# Grove_-_GSR_v1_0.net
KiCad netlist of a schematic drawn in EAGLE
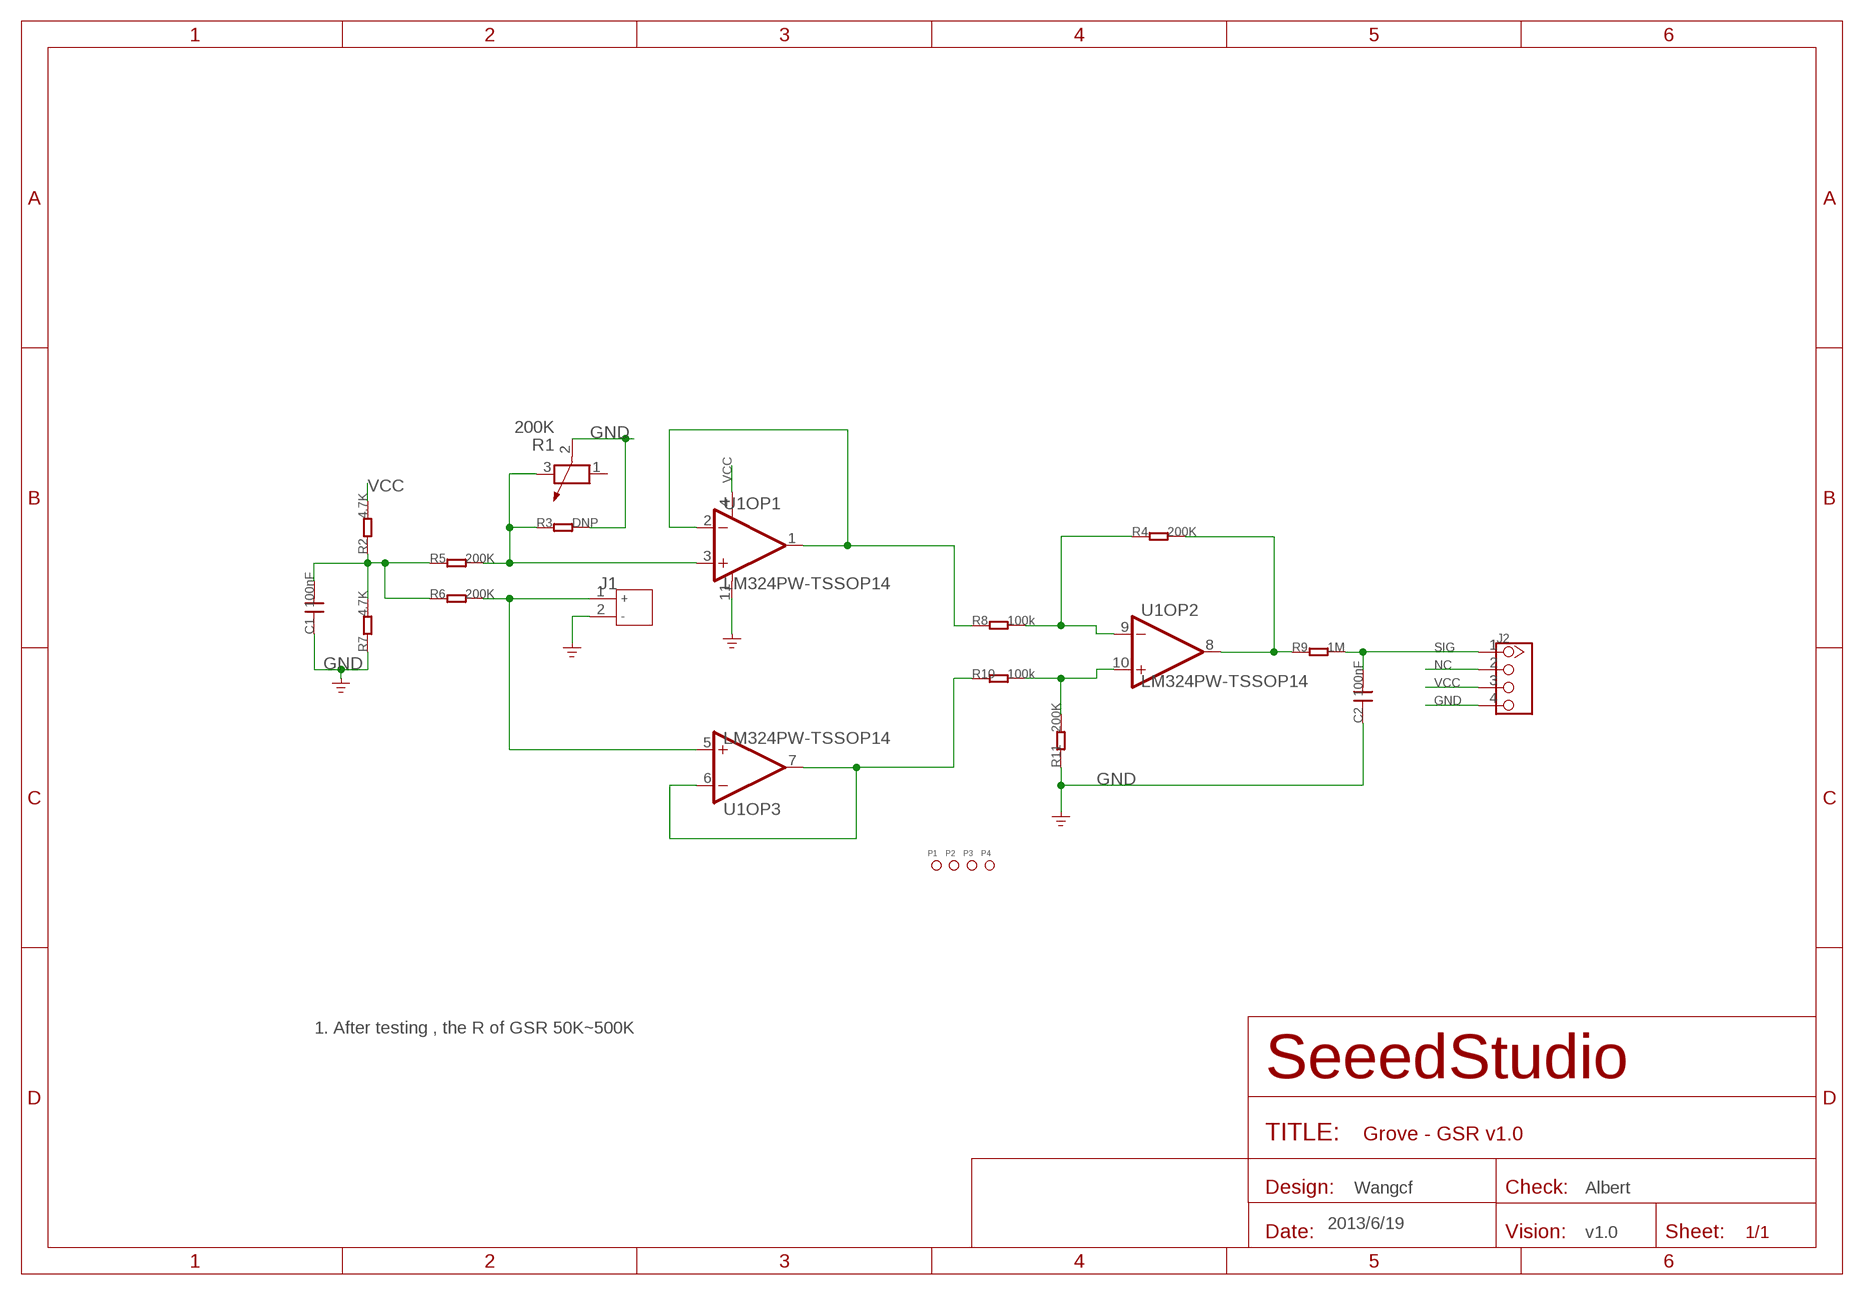
[diagram p0: schematic, sheet 1]

(export (version "E")
  (design (tool "Eeschema 10.0.6"))
  (components
    (comp (ref "C1")
      (value "100nF")
      (footprint "eagle-import:0603")
      (libsource (lib "eagle-import") (part "C-0603"))
    )
    (comp (ref "C2")
      (value "100nF")
      (footprint "eagle-import:0603")
      (libsource (lib "eagle-import") (part "C-0603"))
    )
    (comp (ref "J1")
      (value "JACK-JST-2P-PW'2.0'")
      (footprint "eagle-import:JST-2.0")
      (libsource (lib "eagle-import") (part "JACK-JST-2P-PW'2.0'"))
    )
    (comp (ref "J2")
      (value "TWIG-4P-2.0-2.0")
      (footprint "eagle-import:4P-2.0")
      (libsource (lib "eagle-import") (part "TWIG-4P-2.0-2.0"))
    )
    (comp (ref "P1")
      (value "PAD-MARK")
      (footprint "eagle-import:ROUND-MARK-1.0")
      (fields (field (name "PARTNO") "DNP"))
      (libsource (lib "eagle-import") (part "PAD-MARK"))
    )
    (comp (ref "P2")
      (value "PAD-MARK")
      (footprint "eagle-import:ROUND-MARK-1.0")
      (fields (field (name "PARTNO") "DNP"))
      (libsource (lib "eagle-import") (part "PAD-MARK"))
    )
    (comp (ref "P3")
      (value "PAD-MARK")
      (footprint "eagle-import:ROUND-MARK-1.0")
      (fields (field (name "PARTNO") "DNP"))
      (libsource (lib "eagle-import") (part "PAD-MARK"))
    )
    (comp (ref "P4")
      (value "PAD-MARK")
      (footprint "eagle-import:ROUND-MARK-1.0")
      (fields (field (name "PARTNO") "DNP"))
      (libsource (lib "eagle-import") (part "PAD-MARK"))
    )
    (comp (ref "R1")
      (value "200K")
      (footprint "eagle-import:3P-SMD-RECT-3.3X3.6")
      (libsource (lib "eagle-import") (part "R-POTENTIOMETER-SMD"))
    )
    (comp (ref "R2")
      (value "4.7K")
      (footprint "eagle-import:0603")
      (libsource (lib "eagle-import") (part "R-0603"))
    )
    (comp (ref "R3")
      (value "DNP")
      (footprint "eagle-import:0603")
      (libsource (lib "eagle-import") (part "R-0603"))
    )
    (comp (ref "R4")
      (value "200K")
      (footprint "eagle-import:0603")
      (libsource (lib "eagle-import") (part "R-0603"))
    )
    (comp (ref "R5")
      (value "200K")
      (footprint "eagle-import:0603")
      (libsource (lib "eagle-import") (part "R-0603"))
    )
    (comp (ref "R6")
      (value "200K")
      (footprint "eagle-import:0603")
      (libsource (lib "eagle-import") (part "R-0603"))
    )
    (comp (ref "R7")
      (value "4.7K")
      (footprint "eagle-import:0603")
      (libsource (lib "eagle-import") (part "R-0603"))
    )
    (comp (ref "R8")
      (value "100k")
      (footprint "eagle-import:0603")
      (libsource (lib "eagle-import") (part "R-0603"))
    )
    (comp (ref "R9")
      (value "1M")
      (footprint "eagle-import:0603")
      (libsource (lib "eagle-import") (part "R-0603"))
    )
    (comp (ref "R10")
      (value "100k")
      (footprint "eagle-import:0603")
      (libsource (lib "eagle-import") (part "R-0603"))
    )
    (comp (ref "R11")
      (value "200K")
      (footprint "eagle-import:0603")
      (libsource (lib "eagle-import") (part "R-0603"))
    )
    (comp (ref "U1")
      (value "LM324PW-TSSOP14")
      (footprint "eagle-import:TSSOP14")
      (libsource (lib "eagle-import") (part "LMV324-TSSOP14"))
    )
  )
  (nets
    (net (code "1") (name "/NC") (class "Default")
      (node (ref "J2") (pin "2") (pinfunction "2_2") (pintype "bidirectional"))
    )
    (net (code "2") (name "/SIG") (class "Default")
      (node (ref "C2") (pin "2") (pinfunction "2_2") (pintype "passive"))
      (node (ref "J2") (pin "1") (pinfunction "1_1") (pintype "bidirectional"))
      (node (ref "R9") (pin "2") (pinfunction "2_2") (pintype "passive"))
    )
    (net (code "3") (name "/VCC") (class "Default")
      (node (ref "J2") (pin "3") (pinfunction "3_3") (pintype "bidirectional"))
      (node (ref "R2") (pin "2") (pinfunction "2_2") (pintype "passive"))
      (node (ref "U1") (pin "4") (pinfunction "V+_4") (pintype "power_in"))
    )
    (net (code "4") (name "GND_POWER") (class "Default")
      (node (ref "C1") (pin "1") (pinfunction "1_1") (pintype "passive"))
      (node (ref "C2") (pin "1") (pinfunction "1_1") (pintype "passive"))
      (node (ref "J1") (pin "2") (pinfunction "P$2_2") (pintype "bidirectional"))
      (node (ref "J2") (pin "4") (pinfunction "4_4") (pintype "bidirectional"))
      (node (ref "R1") (pin "2") (pinfunction "3_2") (pintype "passive"))
      (node (ref "R11") (pin "1") (pinfunction "1_1") (pintype "passive"))
      (node (ref "R3") (pin "2") (pinfunction "2_2") (pintype "passive"))
      (node (ref "R7") (pin "1") (pinfunction "1_1") (pintype "passive"))
      (node (ref "U1") (pin "11") (pinfunction "V-_11") (pintype "power_in"))
    )
    (net (code "5") (name "Net-(C1-Pad2)") (class "Default")
      (node (ref "C1") (pin "2") (pinfunction "2_2") (pintype "passive"))
      (node (ref "R2") (pin "1") (pinfunction "1_1") (pintype "passive"))
      (node (ref "R5") (pin "1") (pinfunction "1_1") (pintype "passive"))
      (node (ref "R6") (pin "1") (pinfunction "1_1") (pintype "passive"))
      (node (ref "R7") (pin "2") (pinfunction "2_2") (pintype "passive"))
    )
    (net (code "6") (name "Net-(J1-P$1)") (class "Default")
      (node (ref "J1") (pin "1") (pinfunction "P$1_1") (pintype "bidirectional"))
      (node (ref "R6") (pin "2") (pinfunction "2_2") (pintype "passive"))
      (node (ref "U1") (pin "5") (pinfunction "IN+_5") (pintype "input"))
    )
    (net (code "7") (name "Net-(R1-2)") (class "Default")
      (node (ref "R1") (pin "3") (pinfunction "2_3") (pintype "passive"))
      (node (ref "R3") (pin "1") (pinfunction "1_1") (pintype "passive"))
      (node (ref "R5") (pin "2") (pinfunction "2_2") (pintype "passive"))
      (node (ref "U1") (pin "3") (pinfunction "IN+_3") (pintype "input"))
    )
    (net (code "8") (name "Net-(U1A-IN-)") (class "Default")
      (node (ref "R8") (pin "1") (pinfunction "1_1") (pintype "passive"))
      (node (ref "U1") (pin "1") (pinfunction "OUT_1") (pintype "output"))
      (node (ref "U1") (pin "2") (pinfunction "IN-_2") (pintype "input"))
    )
    (net (code "9") (name "Net-(U1B-IN+)") (class "Default")
      (node (ref "R10") (pin "2") (pinfunction "2_2") (pintype "passive"))
      (node (ref "R11") (pin "2") (pinfunction "2_2") (pintype "passive"))
      (node (ref "U1") (pin "10") (pinfunction "IN+_10") (pintype "input"))
    )
    (net (code "10") (name "Net-(U1B-IN-)") (class "Default")
      (node (ref "R4") (pin "1") (pinfunction "1_1") (pintype "passive"))
      (node (ref "R8") (pin "2") (pinfunction "2_2") (pintype "passive"))
      (node (ref "U1") (pin "9") (pinfunction "IN-_9") (pintype "input"))
    )
    (net (code "11") (name "Net-(U1B-OUT)") (class "Default")
      (node (ref "R4") (pin "2") (pinfunction "2_2") (pintype "passive"))
      (node (ref "R9") (pin "1") (pinfunction "1_1") (pintype "passive"))
      (node (ref "U1") (pin "8") (pinfunction "OUT_8") (pintype "output"))
    )
    (net (code "12") (name "Net-(U1C-IN-)") (class "Default")
      (node (ref "R10") (pin "1") (pinfunction "1_1") (pintype "passive"))
      (node (ref "U1") (pin "6") (pinfunction "IN-_6") (pintype "input"))
      (node (ref "U1") (pin "7") (pinfunction "OUT_7") (pintype "output"))
    )
    (net (code "13") (name "unconnected-(R1-Pad1)") (class "Default")
      (node (ref "R1") (pin "1") (pinfunction "1_1") (pintype "passive"))
    )
  )
)
